# Irnardo_REVA.net
KiCad netlist of a schematic drawn in EAGLE
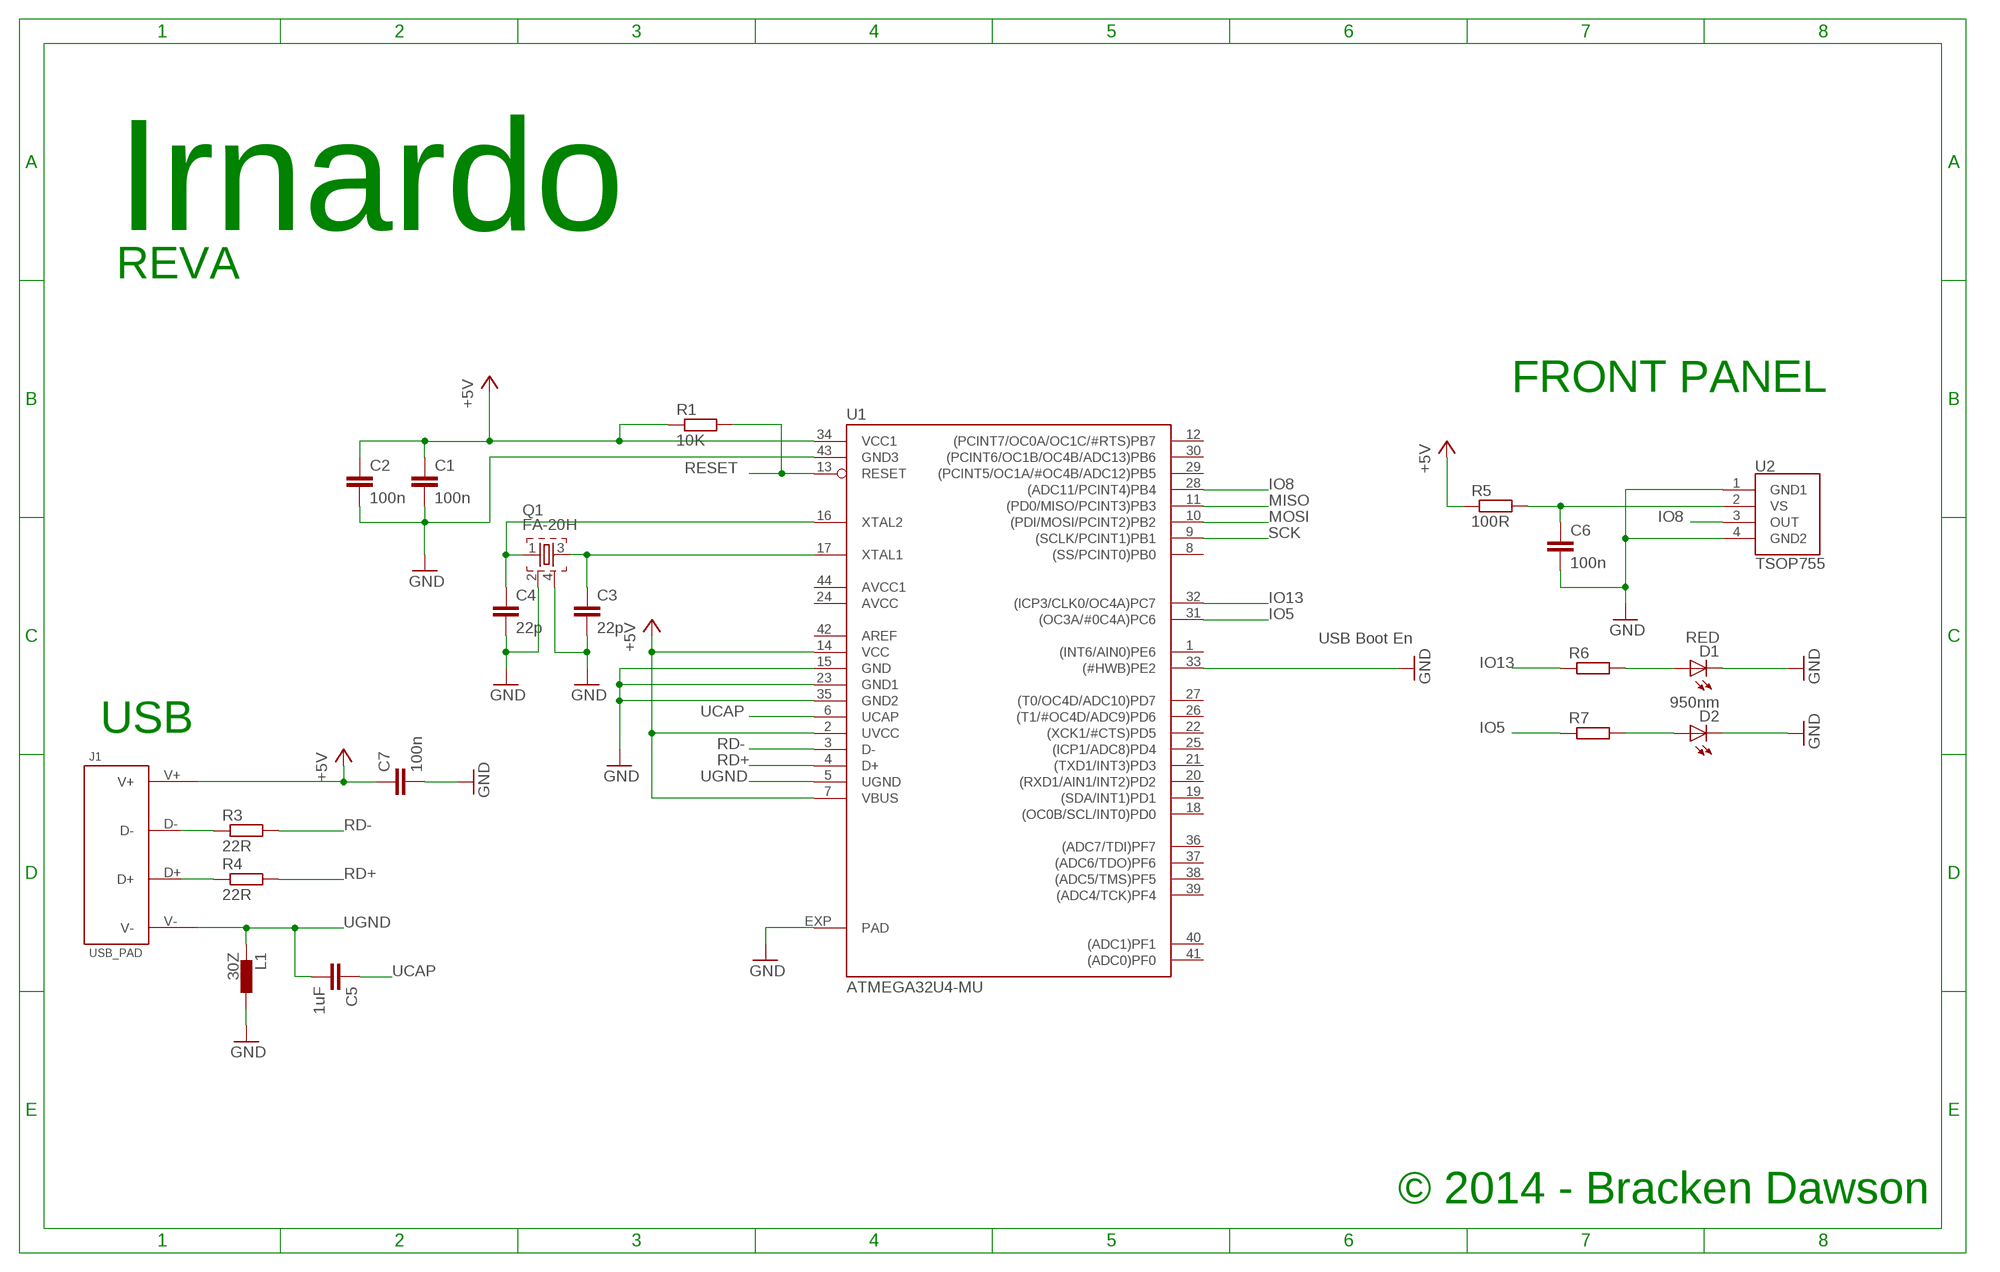
[diagram p0: schematic, sheet 1]

(export (version "E")
  (design (tool "Eeschema 10.0.6"))
  (components
    (comp (ref "C1")
      (value "100n")
      (footprint "eagle-import:C0402")
      (libsource (lib "eagle-import") (part "C-EUC0402"))
    )
    (comp (ref "C2")
      (value "100n")
      (footprint "eagle-import:C0402")
      (libsource (lib "eagle-import") (part "C-EUC0402"))
    )
    (comp (ref "C3")
      (value "22p")
      (footprint "eagle-import:C0402")
      (libsource (lib "eagle-import") (part "C-EUC0402"))
    )
    (comp (ref "C4")
      (value "22p")
      (footprint "eagle-import:C0402")
      (libsource (lib "eagle-import") (part "C-EUC0402"))
    )
    (comp (ref "C5")
      (value "1uF")
      (footprint "eagle-import:C0402")
      (libsource (lib "eagle-import") (part "C-EUC0402"))
    )
    (comp (ref "C6")
      (value "100n")
      (footprint "eagle-import:C0402")
      (libsource (lib "eagle-import") (part "C-EUC0402"))
    )
    (comp (ref "C7")
      (value "100n")
      (footprint "eagle-import:C0402")
      (libsource (lib "eagle-import") (part "C-EUC0402"))
    )
    (comp (ref "D1")
      (value "RED")
      (footprint "eagle-import:SML0603")
      (libsource (lib "eagle-import") (part "LEDSML0603"))
    )
    (comp (ref "D2")
      (value "950nm")
      (footprint "eagle-import:SML0603")
      (libsource (lib "eagle-import") (part "LEDSML0603"))
    )
    (comp (ref "J1")
      (value "USB_PAD")
      (footprint "eagle-import:USB_PAD")
      (libsource (lib "eagle-import") (part "USB_PAD"))
    )
    (comp (ref "L1")
      (value "30Z")
      (footprint "eagle-import:0402")
      (libsource (lib "eagle-import") (part "BLM15HB121SN1"))
    )
    (comp (ref "Q1")
      (value "FA-20H")
      (footprint "eagle-import:FA-20H")
      (libsource (lib "eagle-import") (part "FA-20H"))
    )
    (comp (ref "R1")
      (value "10K")
      (footprint "eagle-import:R0402")
      (libsource (lib "eagle-import") (part "R-EU_R0402"))
    )
    (comp (ref "R3")
      (value "22R")
      (footprint "eagle-import:R0402")
      (libsource (lib "eagle-import") (part "R-EU_R0402"))
    )
    (comp (ref "R4")
      (value "22R")
      (footprint "eagle-import:R0402")
      (libsource (lib "eagle-import") (part "R-EU_R0402"))
    )
    (comp (ref "R5")
      (value "100R")
      (footprint "eagle-import:R0402")
      (libsource (lib "eagle-import") (part "R-EU_R0402"))
    )
    (comp (ref "R6")
      (value "R-EU_R0402")
      (footprint "eagle-import:R0402")
      (libsource (lib "eagle-import") (part "R-EU_R0402"))
    )
    (comp (ref "R7")
      (value "R-EU_R0402")
      (footprint "eagle-import:R0402")
      (libsource (lib "eagle-import") (part "R-EU_R0402"))
    )
    (comp (ref "U1")
      (value "ATMEGA32U4-MU")
      (footprint "eagle-import:SMARTPRJ_QFN44ML7X7")
      (libsource (lib "eagle-import") (part "SMARTPRJ_ATMEGA32U4-XUMU"))
    )
    (comp (ref "U2")
      (value "TSOP755")
      (footprint "eagle-import:TSOP755")
      (libsource (lib "eagle-import") (part "TSOP755"))
    )
  )
  (nets
    (net (code "1") (name "+5V") (class "Default")
      (node (ref "C1") (pin "1") (pinfunction "1_1") (pintype "passive"))
      (node (ref "C2") (pin "1") (pinfunction "1_1") (pintype "passive"))
      (node (ref "C7") (pin "1") (pinfunction "1_1") (pintype "passive"))
      (node (ref "J1") (pin "V+") (pinfunction "V+_V+") (pintype "bidirectional"))
      (node (ref "R1") (pin "1") (pinfunction "1_1") (pintype "passive"))
      (node (ref "R5") (pin "1") (pinfunction "1_1") (pintype "passive"))
      (node (ref "U1") (pin "14") (pinfunction "VCC_14") (pintype "power_in"))
      (node (ref "U1") (pin "2") (pinfunction "UVCC_2") (pintype "power_in"))
      (node (ref "U1") (pin "34") (pinfunction "VCC1_34") (pintype "power_in"))
      (node (ref "U1") (pin "7") (pinfunction "VBUS_7") (pintype "input"))
    )
    (net (code "2") (name "/AREF") (class "Default")
      (node (ref "U1") (pin "42") (pinfunction "AREF_42") (pintype "power_in"))
    )
    (net (code "3") (name "/AVCC") (class "Default")
      (node (ref "U1") (pin "24") (pinfunction "AVCC_24") (pintype "power_in"))
    )
    (net (code "4") (name "/AVCC1") (class "Default")
      (node (ref "U1") (pin "44") (pinfunction "AVCC1_44") (pintype "power_in"))
    )
    (net (code "5") (name "/IO5") (class "Default")
      (node (ref "R7") (pin "1") (pinfunction "1_1") (pintype "passive"))
      (node (ref "U1") (pin "31") (pinfunction "(OC3A/#0C4A)PC6_31") (pintype "bidirectional"))
    )
    (net (code "6") (name "/IO8") (class "Default")
      (node (ref "U1") (pin "28") (pinfunction "(ADC11/PCINT4)PB4_28") (pintype "bidirectional"))
      (node (ref "U2") (pin "3") (pinfunction "OUT_3") (pintype "bidirectional"))
    )
    (net (code "7") (name "/IO13") (class "Default")
      (node (ref "R6") (pin "1") (pinfunction "1_1") (pintype "passive"))
      (node (ref "U1") (pin "32") (pinfunction "(ICP3/CLK0/OC4A)PC7_32") (pintype "bidirectional"))
    )
    (net (code "8") (name "/MISO") (class "Default")
      (node (ref "U1") (pin "11") (pinfunction "(PD0/MISO/PCINT3)PB3_11") (pintype "bidirectional"))
    )
    (net (code "9") (name "/MOSI") (class "Default")
      (node (ref "U1") (pin "10") (pinfunction "(PDI/MOSI/PCINT2)PB2_10") (pintype "bidirectional"))
    )
    (net (code "10") (name "/RD+") (class "Default")
      (node (ref "R4") (pin "2") (pinfunction "2_2") (pintype "passive"))
      (node (ref "U1") (pin "4") (pinfunction "D+_4") (pintype "bidirectional"))
    )
    (net (code "11") (name "/RD-") (class "Default")
      (node (ref "R3") (pin "2") (pinfunction "2_2") (pintype "passive"))
      (node (ref "U1") (pin "3") (pinfunction "D-_3") (pintype "bidirectional"))
    )
    (net (code "12") (name "/RESET") (class "Default")
      (node (ref "R1") (pin "2") (pinfunction "2_2") (pintype "passive"))
      (node (ref "U1") (pin "13") (pinfunction "RESET_13") (pintype "input"))
    )
    (net (code "13") (name "/SCK") (class "Default")
      (node (ref "U1") (pin "9") (pinfunction "(SCLK/PCINT1)PB1_9") (pintype "bidirectional"))
    )
    (net (code "14") (name "/UCAP") (class "Default")
      (node (ref "C5") (pin "1") (pinfunction "1_1") (pintype "passive"))
      (node (ref "U1") (pin "6") (pinfunction "UCAP_6") (pintype "passive"))
    )
    (net (code "15") (name "/UGND") (class "Default")
      (node (ref "C5") (pin "2") (pinfunction "2_2") (pintype "passive"))
      (node (ref "J1") (pin "V-") (pinfunction "V-_V-") (pintype "bidirectional"))
      (node (ref "L1") (pin "1") (pinfunction "1_1") (pintype "passive"))
      (node (ref "U1") (pin "5") (pinfunction "UGND_5") (pintype "power_in"))
    )
    (net (code "16") (name "GND") (class "Default")
      (node (ref "C1") (pin "2") (pinfunction "2_2") (pintype "passive"))
      (node (ref "C2") (pin "2") (pinfunction "2_2") (pintype "passive"))
      (node (ref "C3") (pin "2") (pinfunction "2_2") (pintype "passive"))
      (node (ref "C4") (pin "2") (pinfunction "2_2") (pintype "passive"))
      (node (ref "C6") (pin "2") (pinfunction "2_2") (pintype "passive"))
      (node (ref "C7") (pin "2") (pinfunction "2_2") (pintype "passive"))
      (node (ref "D1") (pin "C") (pinfunction "C_C") (pintype "passive"))
      (node (ref "D2") (pin "C") (pinfunction "C_C") (pintype "passive"))
      (node (ref "L1") (pin "2") (pinfunction "2_2") (pintype "passive"))
      (node (ref "Q1") (pin "2") (pinfunction "2_2") (pintype "passive"))
      (node (ref "Q1") (pin "4") (pinfunction "4_4") (pintype "passive"))
      (node (ref "U1") (pin "15") (pinfunction "GND_15") (pintype "power_in"))
      (node (ref "U1") (pin "23") (pinfunction "GND1_23") (pintype "power_in"))
      (node (ref "U1") (pin "33") (pinfunction "(#HWB)PE2_33") (pintype "bidirectional"))
      (node (ref "U1") (pin "35") (pinfunction "GND2_35") (pintype "power_in"))
      (node (ref "U1") (pin "43") (pinfunction "GND3_43") (pintype "power_in"))
      (node (ref "U1") (pin "EXP") (pinfunction "PAD_EXP") (pintype "power_in"))
      (node (ref "U2") (pin "1") (pinfunction "GND1_1") (pintype "bidirectional"))
      (node (ref "U2") (pin "4") (pinfunction "GND2_4") (pintype "bidirectional"))
    )
    (net (code "17") (name "Net-(D1-PadA)") (class "Default")
      (node (ref "D1") (pin "A") (pinfunction "A_A") (pintype "passive"))
      (node (ref "R6") (pin "2") (pinfunction "2_2") (pintype "passive"))
    )
    (net (code "18") (name "Net-(D2-PadA)") (class "Default")
      (node (ref "D2") (pin "A") (pinfunction "A_A") (pintype "passive"))
      (node (ref "R7") (pin "2") (pinfunction "2_2") (pintype "passive"))
    )
    (net (code "19") (name "Net-(J1-PadD+)") (class "Default")
      (node (ref "J1") (pin "D+") (pinfunction "D+_D+") (pintype "bidirectional"))
      (node (ref "R4") (pin "1") (pinfunction "1_1") (pintype "passive"))
    )
    (net (code "20") (name "Net-(J1-PadD-)") (class "Default")
      (node (ref "J1") (pin "D-") (pinfunction "D-_D-") (pintype "bidirectional"))
      (node (ref "R3") (pin "1") (pinfunction "1_1") (pintype "passive"))
    )
    (net (code "21") (name "Net-(U1-XTAL1)") (class "Default")
      (node (ref "C3") (pin "1") (pinfunction "1_1") (pintype "passive"))
      (node (ref "Q1") (pin "3") (pinfunction "3_3") (pintype "passive"))
      (node (ref "U1") (pin "17") (pinfunction "XTAL1_17") (pintype "bidirectional"))
    )
    (net (code "22") (name "Net-(U1-XTAL2)") (class "Default")
      (node (ref "C4") (pin "1") (pinfunction "1_1") (pintype "passive"))
      (node (ref "Q1") (pin "1") (pinfunction "1_1") (pintype "passive"))
      (node (ref "U1") (pin "16") (pinfunction "XTAL2_16") (pintype "bidirectional"))
    )
    (net (code "23") (name "Net-(U2-VS)") (class "Default")
      (node (ref "C6") (pin "1") (pinfunction "1_1") (pintype "passive"))
      (node (ref "R5") (pin "2") (pinfunction "2_2") (pintype "passive"))
      (node (ref "U2") (pin "2") (pinfunction "VS_2") (pintype "bidirectional"))
    )
    (net (code "24") (name "unconnected-(U1-(ADC0)PF0-Pad41)") (class "Default")
      (node (ref "U1") (pin "41") (pinfunction "(ADC0)PF0_41") (pintype "bidirectional"))
    )
    (net (code "25") (name "unconnected-(U1-(ADC1)PF1-Pad40)") (class "Default")
      (node (ref "U1") (pin "40") (pinfunction "(ADC1)PF1_40") (pintype "bidirectional"))
    )
    (net (code "26") (name "unconnected-(U1-(ADC4{slash}TCK)PF4-Pad39)") (class "Default")
      (node (ref "U1") (pin "39") (pinfunction "(ADC4/TCK)PF4_39") (pintype "bidirectional"))
    )
    (net (code "27") (name "unconnected-(U1-(ADC5{slash}TMS)PF5-Pad38)") (class "Default")
      (node (ref "U1") (pin "38") (pinfunction "(ADC5/TMS)PF5_38") (pintype "bidirectional"))
    )
    (net (code "28") (name "unconnected-(U1-(ADC6{slash}TDO)PF6-Pad37)") (class "Default")
      (node (ref "U1") (pin "37") (pinfunction "(ADC6/TDO)PF6_37") (pintype "bidirectional"))
    )
    (net (code "29") (name "unconnected-(U1-(ADC7{slash}TDI)PF7-Pad36)") (class "Default")
      (node (ref "U1") (pin "36") (pinfunction "(ADC7/TDI)PF7_36") (pintype "bidirectional"))
    )
    (net (code "30") (name "unconnected-(U1-(ICP1{slash}ADC8)PD4-Pad25)") (class "Default")
      (node (ref "U1") (pin "25") (pinfunction "(ICP1/ADC8)PD4_25") (pintype "bidirectional"))
    )
    (net (code "31") (name "unconnected-(U1-(INT6{slash}AIN0)PE6-Pad1)") (class "Default")
      (node (ref "U1") (pin "1") (pinfunction "(INT6/AIN0)PE6_1") (pintype "bidirectional"))
    )
    (net (code "32") (name "unconnected-(U1-(OC0B{slash}SCL{slash}INT0)PD0-Pad18)") (class "Default")
      (node (ref "U1") (pin "18") (pinfunction "(OC0B/SCL/INT0)PD0_18") (pintype "bidirectional"))
    )
    (net (code "33") (name "unconnected-(U1-(PCINT5{slash}OC1A{slash}#OC4B{slash}ADC12)PB5-Pad29)") (class "Default")
      (node (ref "U1") (pin "29") (pinfunction "(PCINT5/OC1A/#OC4B/ADC12)PB5_29") (pintype "bidirectional"))
    )
    (net (code "34") (name "unconnected-(U1-(PCINT6{slash}OC1B{slash}OC4B{slash}ADC13)PB6-Pad30)") (class "Default")
      (node (ref "U1") (pin "30") (pinfunction "(PCINT6/OC1B/OC4B/ADC13)PB6_30") (pintype "bidirectional"))
    )
    (net (code "35") (name "unconnected-(U1-(PCINT7{slash}OC0A{slash}OC1C{slash}#RTS)PB7-Pad12)") (class "Default")
      (node (ref "U1") (pin "12") (pinfunction "(PCINT7/OC0A/OC1C/#RTS)PB7_12") (pintype "bidirectional"))
    )
    (net (code "36") (name "unconnected-(U1-(RXD1{slash}AIN1{slash}INT2)PD2-Pad20)") (class "Default")
      (node (ref "U1") (pin "20") (pinfunction "(RXD1/AIN1/INT2)PD2_20") (pintype "bidirectional"))
    )
    (net (code "37") (name "unconnected-(U1-(SDA{slash}INT1)PD1-Pad19)") (class "Default")
      (node (ref "U1") (pin "19") (pinfunction "(SDA/INT1)PD1_19") (pintype "bidirectional"))
    )
    (net (code "38") (name "unconnected-(U1-(SS{slash}PCINT0)PB0-Pad8)") (class "Default")
      (node (ref "U1") (pin "8") (pinfunction "(SS/PCINT0)PB0_8") (pintype "bidirectional"))
    )
    (net (code "39") (name "unconnected-(U1-(T0{slash}OC4D{slash}ADC10)PD7-Pad27)") (class "Default")
      (node (ref "U1") (pin "27") (pinfunction "(T0/OC4D/ADC10)PD7_27") (pintype "bidirectional"))
    )
    (net (code "40") (name "unconnected-(U1-(T1{slash}#OC4D{slash}ADC9)PD6-Pad26)") (class "Default")
      (node (ref "U1") (pin "26") (pinfunction "(T1/#OC4D/ADC9)PD6_26") (pintype "bidirectional"))
    )
    (net (code "41") (name "unconnected-(U1-(TXD1{slash}INT3)PD3-Pad21)") (class "Default")
      (node (ref "U1") (pin "21") (pinfunction "(TXD1/INT3)PD3_21") (pintype "bidirectional"))
    )
    (net (code "42") (name "unconnected-(U1-(XCK1{slash}#CTS)PD5-Pad22)") (class "Default")
      (node (ref "U1") (pin "22") (pinfunction "(XCK1/#CTS)PD5_22") (pintype "bidirectional"))
    )
  )
)
